# LowduinoSMD_v2.net
KiCad netlist of a schematic drawn in EAGLE
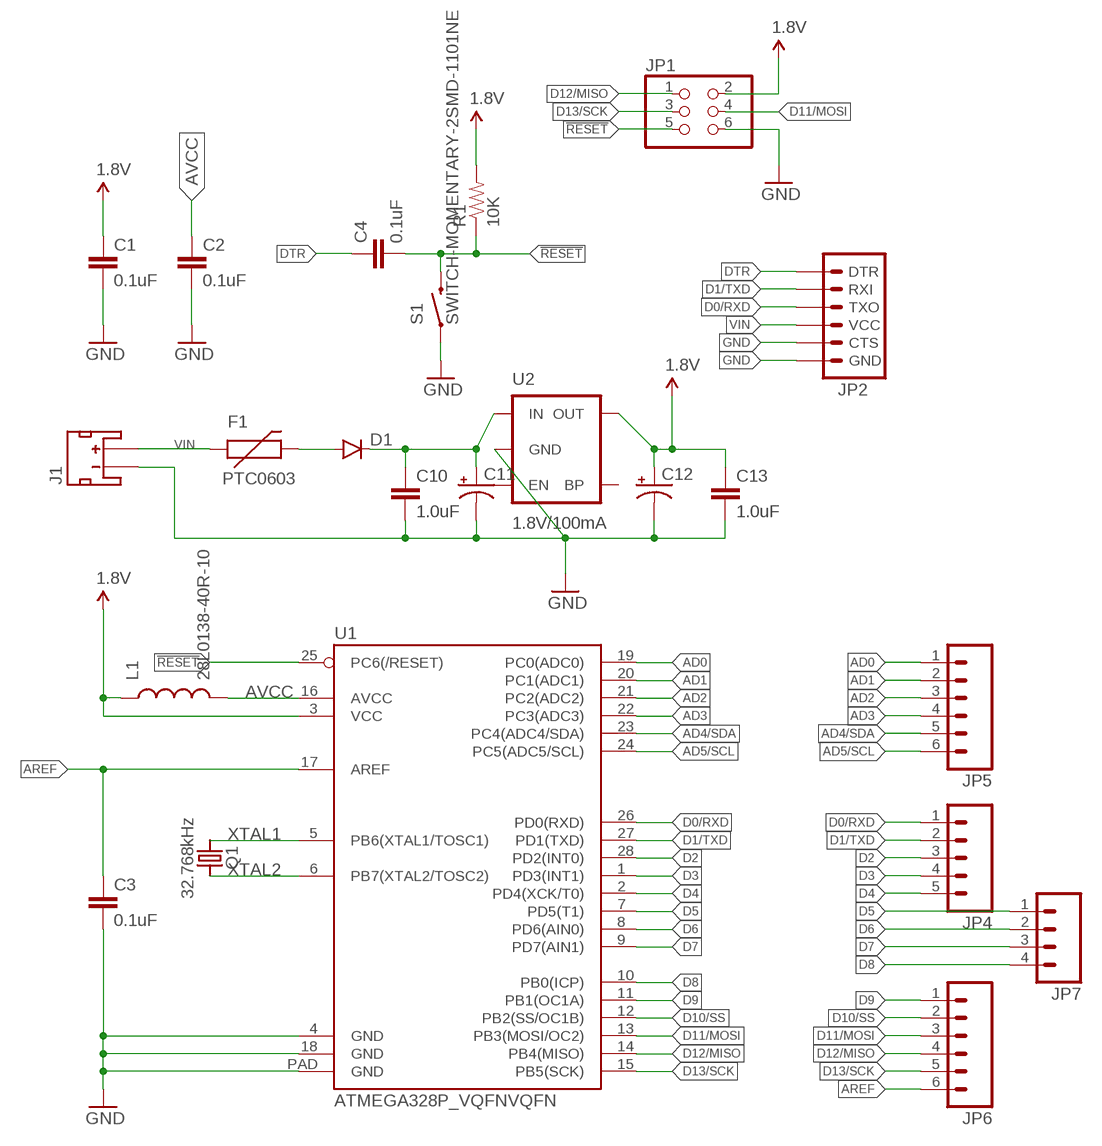
[diagram p0: schematic, sheet 1]

(export (version "E")
  (design (tool "Eeschema 10.0.6"))
  (components
    (comp (ref "C1")
      (value "0.1uF")
      (footprint "eagle-import:0402-CAP")
      (libsource (lib "eagle-import") (part "0.1UF-16V(+-10%)(0402)"))
    )
    (comp (ref "C2")
      (value "0.1uF")
      (footprint "eagle-import:0402-CAP")
      (libsource (lib "eagle-import") (part "0.1UF-16V(+-10%)(0402)"))
    )
    (comp (ref "C3")
      (value "0.1uF")
      (footprint "eagle-import:0402-CAP")
      (libsource (lib "eagle-import") (part "0.1UF-16V(+-10%)(0402)"))
    )
    (comp (ref "C4")
      (value "0.1uF")
      (footprint "eagle-import:0402-CAP")
      (libsource (lib "eagle-import") (part "0.1UF-16V(+-10%)(0402)"))
    )
    (comp (ref "C10")
      (value "1.0uF")
      (footprint "eagle-import:0402-CAP")
      (libsource (lib "eagle-import") (part "1.0UF-16V-10%(0402)"))
    )
    (comp (ref "C11")
      (value "CAP_POLC")
      (footprint "eagle-import:PANASONIC_C")
      (libsource (lib "eagle-import") (part "CAP_POLC"))
    )
    (comp (ref "C12")
      (value "CAP_POLC")
      (footprint "eagle-import:PANASONIC_C")
      (libsource (lib "eagle-import") (part "CAP_POLC"))
    )
    (comp (ref "C13")
      (value "1.0uF")
      (footprint "eagle-import:0402-CAP")
      (libsource (lib "eagle-import") (part "1.0UF-16V-10%(0402)"))
    )
    (comp (ref "D1")
      (value "DIODESOD523")
      (footprint "eagle-import:SOD523")
      (libsource (lib "eagle-import") (part "DIODESOD523"))
    )
    (comp (ref "F1")
      (value "PTC0603")
      (footprint "eagle-import:0603")
      (libsource (lib "eagle-import") (part "PTC0603"))
    )
    (comp (ref "J1")
      (value "JST_2MM_MALE")
      (footprint "eagle-import:JST-2-SMD")
      (libsource (lib "eagle-import") (part "JST_2MM_MALE"))
    )
    (comp (ref "JP1")
      (value "PINHD-2X3")
      (footprint "eagle-import:2X03")
      (libsource (lib "eagle-import") (part "PINHD-2X3"))
    )
    (comp (ref "JP2")
      (value "ARDUINO_SERIAL_PROGRAMPTH")
      (footprint "eagle-import:1X06")
      (libsource (lib "eagle-import") (part "ARDUINO_SERIAL_PROGRAMPTH"))
    )
    (comp (ref "JP4")
      (value "M05NO_SILK")
      (footprint "eagle-import:1X05_NO_SILK")
      (libsource (lib "eagle-import") (part "M05NO_SILK"))
    )
    (comp (ref "JP5")
      (value "M06NO_SILK_FEMALE_PTH")
      (footprint "eagle-import:1X06_NO_SILK")
      (libsource (lib "eagle-import") (part "M06NO_SILK_FEMALE_PTH"))
    )
    (comp (ref "JP6")
      (value "M06NO_SILK_FEMALE_PTH")
      (footprint "eagle-import:1X06_NO_SILK")
      (libsource (lib "eagle-import") (part "M06NO_SILK_FEMALE_PTH"))
    )
    (comp (ref "JP7")
      (value "M04NO_SILK_ALL_ROUND")
      (footprint "eagle-import:1X04_NO_SILK_ALL_ROUND")
      (libsource (lib "eagle-import") (part "M04NO_SILK_ALL_ROUND"))
    )
    (comp (ref "L1")
      (value "28L0138-40R-10")
      (footprint "eagle-import:C0402")
      (libsource (lib "eagle-import") (part "INDUCTOR0402"))
    )
    (comp (ref "Q1")
      (value "32.768kHz")
      (footprint "eagle-import:2-SMD")
      (libsource (lib "eagle-import") (part "FX12232.768KHZ"))
    )
    (comp (ref "R1")
      (value "10K")
      (footprint "eagle-import:0402-RES")
      (libsource (lib "eagle-import") (part "RESISTOR0402"))
    )
    (comp (ref "S1")
      (value "SWITCH-MOMENTARY-2SMD-1101NE")
      (footprint "eagle-import:TACTILE-SWITCH-1101NE")
      (libsource (lib "eagle-import") (part "SWITCH-MOMENTARY-2SMD-1101NE"))
    )
    (comp (ref "U1")
      (value "ATMEGA328P_VQFNVQFN")
      (footprint "eagle-import:VQFN-28")
      (libsource (lib "eagle-import") (part "ATMEGA328P_VQFNVQFN"))
    )
    (comp (ref "U2")
      (value "1.8V/100mA")
      (footprint "eagle-import:SC70")
      (libsource (lib "eagle-import") (part "V_REG_SP62141.8V"))
    )
  )
  (nets
    (net (code "1") (name "/XTAL1") (class "Default")
      (node (ref "Q1") (pin "1") (pinfunction "1_1") (pintype "passive"))
      (node (ref "U1") (pin "5") (pinfunction "PB6(XTAL1/TOSC1)_5") (pintype "bidirectional"))
    )
    (net (code "2") (name "/XTAL2") (class "Default")
      (node (ref "Q1") (pin "2") (pinfunction "2_2") (pintype "passive"))
      (node (ref "U1") (pin "6") (pinfunction "PB7(XTAL2/TOSC2)_6") (pintype "bidirectional"))
    )
    (net (code "3") (name "/~{RESET}") (class "Default")
      (node (ref "C4") (pin "2") (pinfunction "2_2") (pintype "passive"))
      (node (ref "JP1") (pin "5") (pinfunction "5_5") (pintype "passive"))
      (node (ref "R1") (pin "1") (pinfunction "1_1") (pintype "passive"))
      (node (ref "S1") (pin "2") (pinfunction "2_2") (pintype "passive"))
      (node (ref "U1") (pin "25") (pinfunction "PC6(/RESET)_25") (pintype "bidirectional"))
    )
    (net (code "4") (name "1.8V") (class "Default")
      (node (ref "C1") (pin "1") (pinfunction "1_1") (pintype "passive"))
      (node (ref "C12") (pin "+") (pinfunction "+_+") (pintype "passive"))
      (node (ref "C13") (pin "1") (pinfunction "1_1") (pintype "passive"))
      (node (ref "JP1") (pin "2") (pinfunction "2_2") (pintype "passive"))
      (node (ref "L1") (pin "1") (pinfunction "1_1") (pintype "passive"))
      (node (ref "R1") (pin "2") (pinfunction "2_2") (pintype "passive"))
      (node (ref "U1") (pin "3") (pinfunction "VCC_3") (pintype "bidirectional"))
      (node (ref "U2") (pin "5") (pinfunction "OUT_5") (pintype "passive"))
    )
    (net (code "5") (name "AD0") (class "Default")
      (node (ref "JP5") (pin "1") (pinfunction "1_1") (pintype "passive"))
      (node (ref "U1") (pin "19") (pinfunction "PC0(ADC0)_19") (pintype "bidirectional"))
    )
    (net (code "6") (name "AD1") (class "Default")
      (node (ref "JP5") (pin "2") (pinfunction "2_2") (pintype "passive"))
      (node (ref "U1") (pin "20") (pinfunction "PC1(ADC1)_20") (pintype "bidirectional"))
    )
    (net (code "7") (name "AD2") (class "Default")
      (node (ref "JP5") (pin "3") (pinfunction "3_3") (pintype "passive"))
      (node (ref "U1") (pin "21") (pinfunction "PC2(ADC2)_21") (pintype "bidirectional"))
    )
    (net (code "8") (name "AD3") (class "Default")
      (node (ref "JP5") (pin "4") (pinfunction "4_4") (pintype "passive"))
      (node (ref "U1") (pin "22") (pinfunction "PC3(ADC3)_22") (pintype "bidirectional"))
    )
    (net (code "9") (name "AD4{slash}SDA") (class "Default")
      (node (ref "JP5") (pin "5") (pinfunction "5_5") (pintype "passive"))
      (node (ref "U1") (pin "23") (pinfunction "PC4(ADC4/SDA)_23") (pintype "bidirectional"))
    )
    (net (code "10") (name "AD5{slash}SCL") (class "Default")
      (node (ref "JP5") (pin "6") (pinfunction "6_6") (pintype "passive"))
      (node (ref "U1") (pin "24") (pinfunction "PC5(ADC5/SCL)_24") (pintype "bidirectional"))
    )
    (net (code "11") (name "AREF") (class "Default")
      (node (ref "C3") (pin "1") (pinfunction "1_1") (pintype "passive"))
      (node (ref "JP6") (pin "6") (pinfunction "6_6") (pintype "passive"))
      (node (ref "U1") (pin "17") (pinfunction "AREF_17") (pintype "bidirectional"))
    )
    (net (code "12") (name "AVCC") (class "Default")
      (node (ref "C2") (pin "1") (pinfunction "1_1") (pintype "passive"))
      (node (ref "L1") (pin "2") (pinfunction "2_2") (pintype "passive"))
      (node (ref "U1") (pin "16") (pinfunction "AVCC_16") (pintype "bidirectional"))
    )
    (net (code "13") (name "D0{slash}RXD") (class "Default")
      (node (ref "JP2") (pin "3") (pinfunction "TXO_3") (pintype "passive"))
      (node (ref "JP4") (pin "1") (pinfunction "1_1") (pintype "passive"))
      (node (ref "U1") (pin "26") (pinfunction "PD0(RXD)_26") (pintype "bidirectional"))
    )
    (net (code "14") (name "D1{slash}TXD") (class "Default")
      (node (ref "JP2") (pin "2") (pinfunction "RXI_2") (pintype "passive"))
      (node (ref "JP4") (pin "2") (pinfunction "2_2") (pintype "passive"))
      (node (ref "U1") (pin "27") (pinfunction "PD1(TXD)_27") (pintype "bidirectional"))
    )
    (net (code "15") (name "D2") (class "Default")
      (node (ref "JP4") (pin "3") (pinfunction "3_3") (pintype "passive"))
      (node (ref "U1") (pin "28") (pinfunction "PD2(INT0)_28") (pintype "bidirectional"))
    )
    (net (code "16") (name "D3") (class "Default")
      (node (ref "JP4") (pin "4") (pinfunction "4_4") (pintype "passive"))
      (node (ref "U1") (pin "1") (pinfunction "PD3(INT1)_1") (pintype "bidirectional"))
    )
    (net (code "17") (name "D4") (class "Default")
      (node (ref "JP4") (pin "5") (pinfunction "5_5") (pintype "passive"))
      (node (ref "U1") (pin "2") (pinfunction "PD4(XCK/T0)_2") (pintype "bidirectional"))
    )
    (net (code "18") (name "D5") (class "Default")
      (node (ref "JP7") (pin "1") (pinfunction "1_1") (pintype "passive"))
      (node (ref "U1") (pin "7") (pinfunction "PD5(T1)_7") (pintype "bidirectional"))
    )
    (net (code "19") (name "D6") (class "Default")
      (node (ref "JP7") (pin "2") (pinfunction "2_2") (pintype "passive"))
      (node (ref "U1") (pin "8") (pinfunction "PD6(AIN0)_8") (pintype "bidirectional"))
    )
    (net (code "20") (name "D7") (class "Default")
      (node (ref "JP7") (pin "3") (pinfunction "3_3") (pintype "passive"))
      (node (ref "U1") (pin "9") (pinfunction "PD7(AIN1)_9") (pintype "bidirectional"))
    )
    (net (code "21") (name "D8") (class "Default")
      (node (ref "JP7") (pin "4") (pinfunction "4_4") (pintype "passive"))
      (node (ref "U1") (pin "10") (pinfunction "PB0(ICP)_10") (pintype "bidirectional"))
    )
    (net (code "22") (name "D9") (class "Default")
      (node (ref "JP6") (pin "1") (pinfunction "1_1") (pintype "passive"))
      (node (ref "U1") (pin "11") (pinfunction "PB1(OC1A)_11") (pintype "bidirectional"))
    )
    (net (code "23") (name "D10{slash}SS") (class "Default")
      (node (ref "JP6") (pin "2") (pinfunction "2_2") (pintype "passive"))
      (node (ref "U1") (pin "12") (pinfunction "PB2(SS/OC1B)_12") (pintype "bidirectional"))
    )
    (net (code "24") (name "D11{slash}MOSI") (class "Default")
      (node (ref "JP1") (pin "4") (pinfunction "4_4") (pintype "passive"))
      (node (ref "JP6") (pin "3") (pinfunction "3_3") (pintype "passive"))
      (node (ref "U1") (pin "13") (pinfunction "PB3(MOSI/OC2)_13") (pintype "bidirectional"))
    )
    (net (code "25") (name "D12{slash}MISO") (class "Default")
      (node (ref "JP1") (pin "1") (pinfunction "1_1") (pintype "passive"))
      (node (ref "JP6") (pin "4") (pinfunction "4_4") (pintype "passive"))
      (node (ref "U1") (pin "14") (pinfunction "PB4(MISO)_14") (pintype "bidirectional"))
    )
    (net (code "26") (name "D13{slash}SCK") (class "Default")
      (node (ref "JP1") (pin "3") (pinfunction "3_3") (pintype "passive"))
      (node (ref "JP6") (pin "5") (pinfunction "5_5") (pintype "passive"))
      (node (ref "U1") (pin "15") (pinfunction "PB5(SCK)_15") (pintype "bidirectional"))
    )
    (net (code "27") (name "DTR") (class "Default")
      (node (ref "C4") (pin "1") (pinfunction "1_1") (pintype "passive"))
      (node (ref "JP2") (pin "1") (pinfunction "DTR_1") (pintype "passive"))
    )
    (net (code "28") (name "GND") (class "Default")
      (node (ref "C1") (pin "2") (pinfunction "2_2") (pintype "passive"))
      (node (ref "C10") (pin "2") (pinfunction "2_2") (pintype "passive"))
      (node (ref "C11") (pin "-") (pinfunction "-_-") (pintype "passive"))
      (node (ref "C12") (pin "-") (pinfunction "-_-") (pintype "passive"))
      (node (ref "C13") (pin "2") (pinfunction "2_2") (pintype "passive"))
      (node (ref "C2") (pin "2") (pinfunction "2_2") (pintype "passive"))
      (node (ref "C3") (pin "2") (pinfunction "2_2") (pintype "passive"))
      (node (ref "J1") (pin "1") (pinfunction "-_1") (pintype "bidirectional"))
      (node (ref "JP1") (pin "6") (pinfunction "6_6") (pintype "passive"))
      (node (ref "JP2") (pin "5") (pinfunction "CTS_5") (pintype "passive"))
      (node (ref "JP2") (pin "6") (pinfunction "GND_6") (pintype "passive"))
      (node (ref "S1") (pin "1") (pinfunction "1_1") (pintype "passive"))
      (node (ref "U1") (pin "18") (pinfunction "GND_18") (pintype "bidirectional"))
      (node (ref "U1") (pin "4") (pinfunction "GND_4") (pintype "bidirectional"))
      (node (ref "U1") (pin "PAD") (pinfunction "GND_PAD") (pintype "bidirectional"))
      (node (ref "U2") (pin "2") (pinfunction "GND_2") (pintype "input"))
    )
    (net (code "29") (name "Net-(D1-PadA)") (class "Default")
      (node (ref "D1") (pin "A") (pinfunction "A_A") (pintype "passive"))
      (node (ref "F1") (pin "2") (pinfunction "2_2") (pintype "bidirectional"))
    )
    (net (code "30") (name "Net-(U2-IN)") (class "Default")
      (node (ref "C10") (pin "1") (pinfunction "1_1") (pintype "passive"))
      (node (ref "C11") (pin "+") (pinfunction "+_+") (pintype "passive"))
      (node (ref "D1") (pin "C") (pinfunction "C_C") (pintype "passive"))
      (node (ref "U2") (pin "1") (pinfunction "IN_1") (pintype "input"))
    )
    (net (code "31") (name "VIN") (class "Default")
      (node (ref "F1") (pin "1") (pinfunction "1_1") (pintype "bidirectional"))
      (node (ref "J1") (pin "2") (pinfunction "+_2") (pintype "bidirectional"))
      (node (ref "JP2") (pin "4") (pinfunction "VCC_4") (pintype "passive"))
    )
    (net (code "32") (name "unconnected-(J1-PAD1-PadNC1)") (class "Default")
      (node (ref "J1") (pin "NC1") (pinfunction "PAD1_NC1") (pintype "bidirectional"))
    )
    (net (code "33") (name "unconnected-(J1-PAD2-PadNC2)") (class "Default")
      (node (ref "J1") (pin "NC2") (pinfunction "PAD2_NC2") (pintype "bidirectional"))
    )
    (net (code "34") (name "unconnected-(U2-BP-Pad4)") (class "Default")
      (node (ref "U2") (pin "4") (pinfunction "BP_4") (pintype "input"))
    )
    (net (code "35") (name "unconnected-(U2-EN-Pad3)") (class "Default")
      (node (ref "U2") (pin "3") (pinfunction "EN_3") (pintype "input"))
    )
  )
)
